# Double_Socket_TEMPORARY.net
KiCad netlist of a schematic drawn in EAGLE
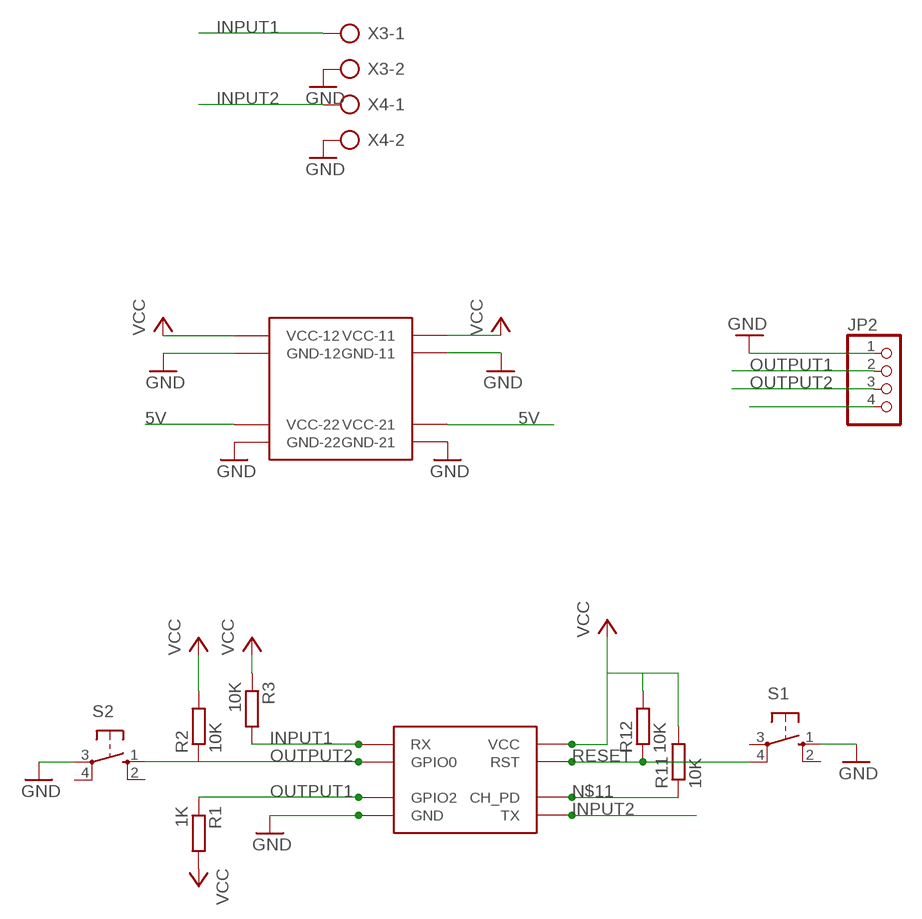
[diagram p0: schematic, sheet 1]

(export (version "E")
  (design (tool "Eeschema 10.0.6"))
  (components
    (comp (ref "JP2")
      (value "PINHD-1X4")
      (footprint "eagle-import:1X04")
      (libsource (lib "eagle-import") (part "PINHD-1X4"))
    )
    (comp (ref "R1")
      (value "1K")
      (footprint "eagle-import:0207_10")
      (libsource (lib "eagle-import") (part "R-EU_0207/10"))
    )
    (comp (ref "R2")
      (value "10K")
      (footprint "eagle-import:0207_10")
      (libsource (lib "eagle-import") (part "R-EU_0207/10"))
    )
    (comp (ref "R3")
      (value "10K")
      (footprint "eagle-import:0207_10")
      (libsource (lib "eagle-import") (part "R-EU_0207/10"))
    )
    (comp (ref "R11")
      (value "10K")
      (footprint "eagle-import:0207_10")
      (libsource (lib "eagle-import") (part "R-EU_0207/10"))
    )
    (comp (ref "R12")
      (value "10K")
      (footprint "eagle-import:0207_10")
      (libsource (lib "eagle-import") (part "R-EU_0207/10"))
    )
    (comp (ref "S1")
      (value "40-XX")
      (footprint "eagle-import:B3F-40XX")
      (fields
        (field (name "MF") "OMRON COMPONENTS USA")
        (field (name "MPN") "B3F-4000")
        (field (name "MF_1") "OMRON COMPONENTS USA")
        (field (name "MPN_1") "B3F-4000")
        (field (name "OC_FARNELL") "176434")
        (field (name "OC_NEWARK") "36K3105")
      )
      (libsource (lib "eagle-import") (part "40-XX"))
    )
    (comp (ref "S2")
      (value "40-XX")
      (footprint "eagle-import:B3F-40XX")
      (fields
        (field (name "MF") "OMRON COMPONENTS USA")
        (field (name "MPN") "B3F-4000")
        (field (name "MF_1") "OMRON COMPONENTS USA")
        (field (name "MPN_1") "B3F-4000")
        (field (name "OC_FARNELL") "176434")
        (field (name "OC_NEWARK") "36K3105")
      )
      (libsource (lib "eagle-import") (part "40-XX"))
    )
    (comp (ref "U$1")
      (value "YWROBOT")
      (footprint "eagle-import:YWROBOT")
      (libsource (lib "eagle-import") (part "YWROBOT"))
    )
    (comp (ref "U$2")
      (value "ESP8266")
      (footprint "eagle-import:ESP8266")
      (libsource (lib "eagle-import") (part "ESP8266"))
    )
    (comp (ref "X3")
      (value "AK500/2-H")
      (footprint "eagle-import:AK500_2-H")
      (libsource (lib "eagle-import") (part "AK500/2-H"))
    )
    (comp (ref "X4")
      (value "AK500/2-H")
      (footprint "eagle-import:AK500_2-H")
      (libsource (lib "eagle-import") (part "AK500/2-H"))
    )
  )
  (nets
    (net (code "1") (name "/5V") (class "Default")
      (node (ref "JP2") (pin "4") (pinfunction "4_4") (pintype "passive"))
      (node (ref "U$1") (pin "VCC-21") (pinfunction "VCC-21_VCC-21") (pintype "bidirectional"))
      (node (ref "U$1") (pin "VCC-22") (pinfunction "VCC-22_VCC-22") (pintype "bidirectional"))
    )
    (net (code "2") (name "/INPUT1") (class "Default")
      (node (ref "R3") (pin "2") (pinfunction "2_2") (pintype "passive"))
      (node (ref "U$2") (pin "RX") (pinfunction "RX_RX") (pintype "bidirectional"))
      (node (ref "X3") (pin "1") (pinfunction "KL_1") (pintype "passive"))
    )
    (net (code "3") (name "/INPUT2") (class "Default")
      (node (ref "U$2") (pin "TX") (pinfunction "TX_TX") (pintype "bidirectional"))
      (node (ref "X4") (pin "1") (pinfunction "KL_1") (pintype "passive"))
    )
    (net (code "4") (name "/N$11") (class "Default")
      (node (ref "R11") (pin "1") (pinfunction "1_1") (pintype "passive"))
      (node (ref "U$2") (pin "CH_PD") (pinfunction "CH_PD_CH_PD") (pintype "bidirectional"))
    )
    (net (code "5") (name "/OUTPUT1") (class "Default")
      (node (ref "JP2") (pin "2") (pinfunction "2_2") (pintype "passive"))
      (node (ref "R1") (pin "1") (pinfunction "1_1") (pintype "passive"))
      (node (ref "U$2") (pin "GPIO2") (pinfunction "GPIO2_GPIO2") (pintype "bidirectional"))
    )
    (net (code "6") (name "/OUTPUT2") (class "Default")
      (node (ref "JP2") (pin "3") (pinfunction "3_3") (pintype "passive"))
      (node (ref "R2") (pin "1") (pinfunction "1_1") (pintype "passive"))
      (node (ref "S2") (pin "1") (pinfunction "S_1") (pintype "passive"))
      (node (ref "U$2") (pin "GPIO0") (pinfunction "GPIO0_GPIO0") (pintype "bidirectional"))
    )
    (net (code "7") (name "/RESET") (class "Default")
      (node (ref "R12") (pin "1") (pinfunction "1_1") (pintype "passive"))
      (node (ref "S1") (pin "4") (pinfunction "P1_4") (pintype "passive"))
      (node (ref "U$2") (pin "RST") (pinfunction "RST_RST") (pintype "bidirectional"))
    )
    (net (code "8") (name "GND") (class "Default")
      (node (ref "JP2") (pin "1") (pinfunction "1_1") (pintype "passive"))
      (node (ref "S1") (pin "1") (pinfunction "S_1") (pintype "passive"))
      (node (ref "S2") (pin "3") (pinfunction "P_3") (pintype "passive"))
      (node (ref "U$1") (pin "GND-11") (pinfunction "GND-11_GND-11") (pintype "bidirectional"))
      (node (ref "U$1") (pin "GND-12") (pinfunction "GND-12_GND-12") (pintype "bidirectional"))
      (node (ref "U$1") (pin "GND-21") (pinfunction "GND-21_GND-21") (pintype "bidirectional"))
      (node (ref "U$1") (pin "GND-22") (pinfunction "GND-22_GND-22") (pintype "bidirectional"))
      (node (ref "U$2") (pin "GND") (pinfunction "GND_GND") (pintype "bidirectional"))
      (node (ref "X3") (pin "2") (pinfunction "KL_2") (pintype "passive"))
      (node (ref "X4") (pin "2") (pinfunction "KL_2") (pintype "passive"))
    )
    (net (code "9") (name "VCC") (class "Default")
      (node (ref "R1") (pin "2") (pinfunction "2_2") (pintype "passive"))
      (node (ref "R11") (pin "2") (pinfunction "2_2") (pintype "passive"))
      (node (ref "R12") (pin "2") (pinfunction "2_2") (pintype "passive"))
      (node (ref "R2") (pin "2") (pinfunction "2_2") (pintype "passive"))
      (node (ref "R3") (pin "1") (pinfunction "1_1") (pintype "passive"))
      (node (ref "U$1") (pin "VCC-11") (pinfunction "VCC-11_VCC-11") (pintype "bidirectional"))
      (node (ref "U$1") (pin "VCC-12") (pinfunction "VCC-12_VCC-12") (pintype "bidirectional"))
      (node (ref "U$2") (pin "VCC") (pinfunction "VCC_VCC") (pintype "bidirectional"))
    )
    (net (code "10") (name "unconnected-(S1-P-Pad3)") (class "Default")
      (node (ref "S1") (pin "3") (pinfunction "P_3") (pintype "passive"))
    )
    (net (code "11") (name "unconnected-(S1-S1-Pad2)") (class "Default")
      (node (ref "S1") (pin "2") (pinfunction "S1_2") (pintype "passive"))
    )
    (net (code "12") (name "unconnected-(S2-P1-Pad4)") (class "Default")
      (node (ref "S2") (pin "4") (pinfunction "P1_4") (pintype "passive"))
    )
    (net (code "13") (name "unconnected-(S2-S1-Pad2)") (class "Default")
      (node (ref "S2") (pin "2") (pinfunction "S1_2") (pintype "passive"))
    )
  )
)
